# printer.net
KiCad netlist of a schematic drawn in EAGLE
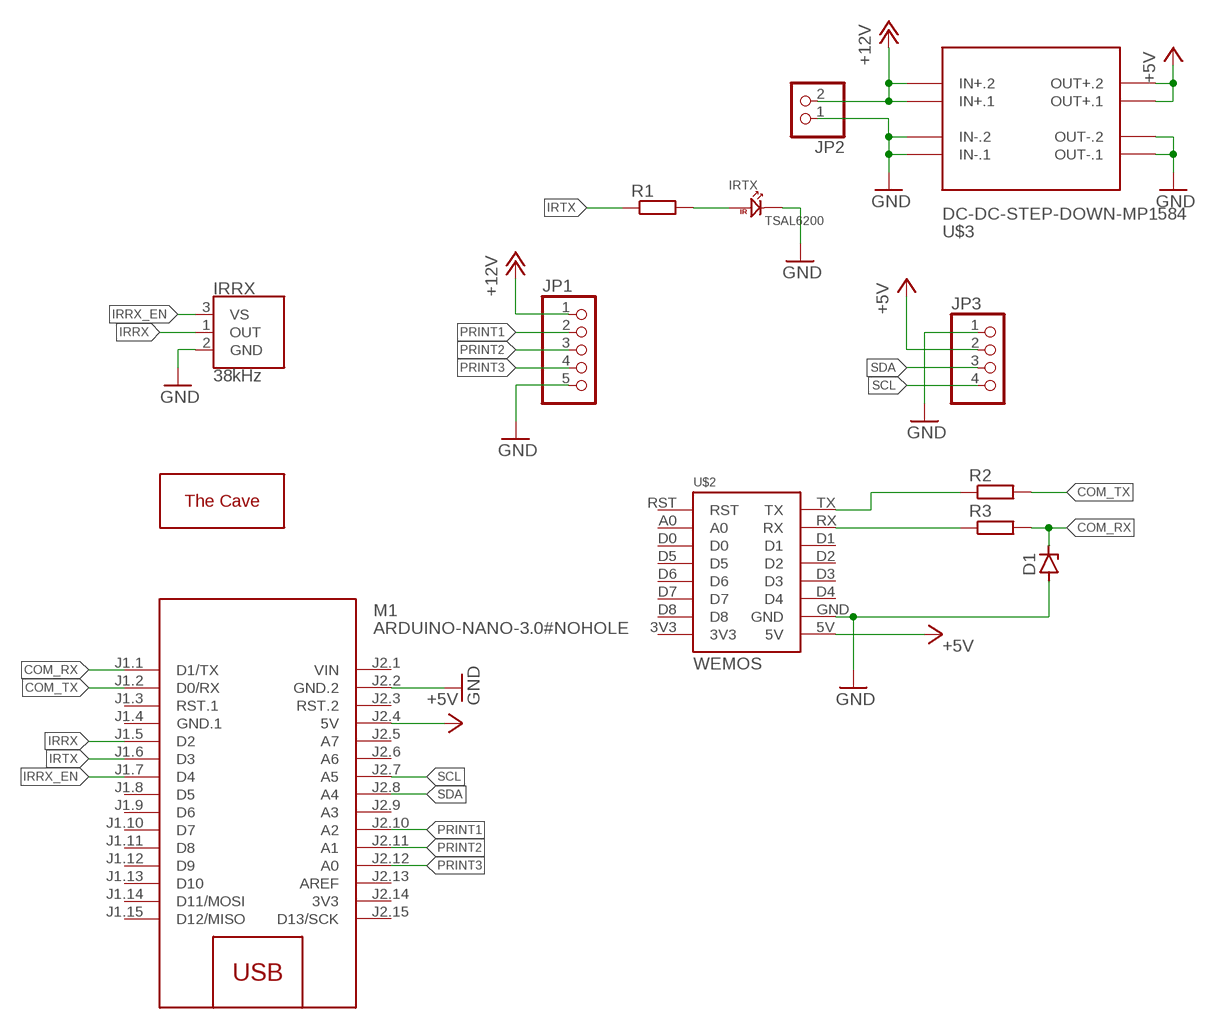
[diagram p0: schematic, sheet 1]

(export (version "E")
  (design (tool "Eeschema 10.0.6"))
  (components
    (comp (ref "D1")
      (value "ZENER-DIODEDO34-7")
      (footprint "eagle-import:DO34Z7")
      (libsource (lib "eagle-import") (part "ZENER-DIODEDO34-7"))
    )
    (comp (ref "IRRX")
      (value "38kHz")
      (footprint "eagle-import:TSOP382")
      (libsource (lib "eagle-import") (part "TSOP38238"))
    )
    (comp (ref "IRTX")
      (value "TSAL6200")
      (footprint "eagle-import:TSAL6200")
      (libsource (lib "eagle-import") (part "TSAL6200"))
    )
    (comp (ref "JP1")
      (value "PINHD-1X5")
      (footprint "eagle-import:1X05")
      (libsource (lib "eagle-import") (part "PINHD-1X5"))
    )
    (comp (ref "JP2")
      (value "PINHD-1X2")
      (footprint "eagle-import:1X02")
      (libsource (lib "eagle-import") (part "PINHD-1X2"))
    )
    (comp (ref "JP3")
      (value "PINHD-1X4")
      (footprint "eagle-import:1X04")
      (libsource (lib "eagle-import") (part "PINHD-1X4"))
    )
    (comp (ref "M1")
      (value "ARDUINO-NANO-3.0#NOHOLE")
      (footprint "eagle-import:ARDUINO-NANO-3.0")
      (libsource (lib "eagle-import") (part "ARDUINO-NANO-3.0#NOHOLE"))
    )
    (comp (ref "R1")
      (value "R-EU_0207/7")
      (footprint "eagle-import:0207_7")
      (libsource (lib "eagle-import") (part "R-EU_0207/7"))
    )
    (comp (ref "R2")
      (value "R-EU_0207/7")
      (footprint "eagle-import:0207_7")
      (libsource (lib "eagle-import") (part "R-EU_0207/7"))
    )
    (comp (ref "R3")
      (value "R-EU_0207/7")
      (footprint "eagle-import:0207_7")
      (libsource (lib "eagle-import") (part "R-EU_0207/7"))
    )
    (comp (ref "U$2")
      (value "WEMOS")
      (footprint "eagle-import:WEMOS")
      (libsource (lib "eagle-import") (part "WEMOS"))
    )
    (comp (ref "U$3")
      (value "DC-DC-STEP-DOWN-MP1584")
      (footprint "eagle-import:DC-DC-STEP-DOWN-MP1584")
      (libsource (lib "eagle-import") (part "DC-DC-STEP-DOWN-MP1584"))
    )
    (comp (ref "U$4")
      (value "THECAVE_LOGO_NEW_BOTTOM")
      (footprint "eagle-import:NEW_LOGO_BOTTOM")
      (libsource (lib "eagle-import") (part "THECAVE_LOGO_NEW_BOTTOM"))
    )
  )
  (nets
    (net (code "1") (name "+5V") (class "Default")
      (node (ref "JP3") (pin "2") (pinfunction "2_2") (pintype "passive"))
      (node (ref "M1") (pin "J2.4") (pinfunction "5V_J2.4") (pintype "power_in"))
      (node (ref "U$2") (pin "5V") (pinfunction "5V_5V") (pintype "bidirectional"))
      (node (ref "U$3") (pin "OUT+.1") (pinfunction "OUT+.1_OUT+.1") (pintype "bidirectional"))
      (node (ref "U$3") (pin "OUT+.2") (pinfunction "OUT+.2_OUT+.2") (pintype "bidirectional"))
    )
    (net (code "2") (name "+12V") (class "Default")
      (node (ref "JP1") (pin "1") (pinfunction "1_1") (pintype "passive"))
      (node (ref "JP2") (pin "2") (pinfunction "2_2") (pintype "passive"))
      (node (ref "U$3") (pin "IN+.1") (pinfunction "IN+.1_IN+.1") (pintype "bidirectional"))
      (node (ref "U$3") (pin "IN+.2") (pinfunction "IN+.2_IN+.2") (pintype "bidirectional"))
    )
    (net (code "3") (name "/3V3") (class "Default")
      (node (ref "M1") (pin "J2.14") (pinfunction "3V3_J2.14") (pintype "power_in"))
    )
    (net (code "4") (name "/GND.1") (class "Default")
      (node (ref "M1") (pin "J1.4") (pinfunction "GND.1_J1.4") (pintype "power_in"))
    )
    (net (code "5") (name "/VIN") (class "Default")
      (node (ref "M1") (pin "J2.1") (pinfunction "VIN_J2.1") (pintype "power_in"))
    )
    (net (code "6") (name "COM_RX") (class "Default")
      (node (ref "D1") (pin "C") (pinfunction "C_C") (pintype "passive"))
      (node (ref "M1") (pin "J1.1") (pinfunction "D1/TX_J1.1") (pintype "bidirectional"))
      (node (ref "R3") (pin "2") (pinfunction "2_2") (pintype "passive"))
    )
    (net (code "7") (name "COM_TX") (class "Default")
      (node (ref "M1") (pin "J1.2") (pinfunction "D0/RX_J1.2") (pintype "bidirectional"))
      (node (ref "R2") (pin "2") (pinfunction "2_2") (pintype "passive"))
    )
    (net (code "8") (name "GND") (class "Default")
      (node (ref "D1") (pin "A") (pinfunction "A_A") (pintype "passive"))
      (node (ref "IRRX") (pin "2") (pinfunction "GND_2") (pintype "bidirectional"))
      (node (ref "IRTX") (pin "N") (pinfunction "N_N") (pintype "bidirectional"))
      (node (ref "JP1") (pin "5") (pinfunction "5_5") (pintype "passive"))
      (node (ref "JP2") (pin "1") (pinfunction "1_1") (pintype "passive"))
      (node (ref "JP3") (pin "1") (pinfunction "1_1") (pintype "passive"))
      (node (ref "M1") (pin "J2.2") (pinfunction "GND.2_J2.2") (pintype "power_in"))
      (node (ref "U$2") (pin "GND") (pinfunction "GND_GND") (pintype "bidirectional"))
      (node (ref "U$3") (pin "IN-.1") (pinfunction "IN-.1_IN-.1") (pintype "bidirectional"))
      (node (ref "U$3") (pin "IN-.2") (pinfunction "IN-.2_IN-.2") (pintype "bidirectional"))
      (node (ref "U$3") (pin "OUT-.1") (pinfunction "OUT-.1_OUT-.1") (pintype "bidirectional"))
      (node (ref "U$3") (pin "OUT-.2") (pinfunction "OUT-.2_OUT-.2") (pintype "bidirectional"))
    )
    (net (code "9") (name "IRRX") (class "Default")
      (node (ref "IRRX") (pin "1") (pinfunction "OUT_1") (pintype "bidirectional"))
      (node (ref "M1") (pin "J1.5") (pinfunction "D2_J1.5") (pintype "bidirectional"))
    )
    (net (code "10") (name "IRRX_EN") (class "Default")
      (node (ref "IRRX") (pin "3") (pinfunction "VS_3") (pintype "bidirectional"))
      (node (ref "M1") (pin "J1.7") (pinfunction "D4_J1.7") (pintype "bidirectional"))
    )
    (net (code "11") (name "IRTX") (class "Default")
      (node (ref "M1") (pin "J1.6") (pinfunction "D3_J1.6") (pintype "bidirectional"))
      (node (ref "R1") (pin "1") (pinfunction "1_1") (pintype "passive"))
    )
    (net (code "12") (name "Net-(IRTX-PadP)") (class "Default")
      (node (ref "IRTX") (pin "P") (pinfunction "P_P") (pintype "bidirectional"))
      (node (ref "R1") (pin "2") (pinfunction "2_2") (pintype "passive"))
    )
    (net (code "13") (name "Net-(R2-Pad1)") (class "Default")
      (node (ref "R2") (pin "1") (pinfunction "1_1") (pintype "passive"))
      (node (ref "U$2") (pin "TX") (pinfunction "TX_TX") (pintype "bidirectional"))
    )
    (net (code "14") (name "Net-(R3-Pad1)") (class "Default")
      (node (ref "R3") (pin "1") (pinfunction "1_1") (pintype "passive"))
      (node (ref "U$2") (pin "RX") (pinfunction "RX_RX") (pintype "bidirectional"))
    )
    (net (code "15") (name "PRINT1") (class "Default")
      (node (ref "JP1") (pin "2") (pinfunction "2_2") (pintype "passive"))
      (node (ref "M1") (pin "J2.10") (pinfunction "A2_J2.10") (pintype "bidirectional"))
    )
    (net (code "16") (name "PRINT2") (class "Default")
      (node (ref "JP1") (pin "3") (pinfunction "3_3") (pintype "passive"))
      (node (ref "M1") (pin "J2.11") (pinfunction "A1_J2.11") (pintype "bidirectional"))
    )
    (net (code "17") (name "PRINT3") (class "Default")
      (node (ref "JP1") (pin "4") (pinfunction "4_4") (pintype "passive"))
      (node (ref "M1") (pin "J2.12") (pinfunction "A0_J2.12") (pintype "bidirectional"))
    )
    (net (code "18") (name "SCL") (class "Default")
      (node (ref "JP3") (pin "4") (pinfunction "4_4") (pintype "passive"))
      (node (ref "M1") (pin "J2.7") (pinfunction "A5_J2.7") (pintype "bidirectional"))
    )
    (net (code "19") (name "SDA") (class "Default")
      (node (ref "JP3") (pin "3") (pinfunction "3_3") (pintype "passive"))
      (node (ref "M1") (pin "J2.8") (pinfunction "A4_J2.8") (pintype "bidirectional"))
    )
    (net (code "20") (name "unconnected-(M1-A3-PadJ2.9)") (class "Default")
      (node (ref "M1") (pin "J2.9") (pinfunction "A3_J2.9") (pintype "bidirectional"))
    )
    (net (code "21") (name "unconnected-(M1-A6-PadJ2.6)") (class "Default")
      (node (ref "M1") (pin "J2.6") (pinfunction "A6_J2.6") (pintype "bidirectional"))
    )
    (net (code "22") (name "unconnected-(M1-A7-PadJ2.5)") (class "Default")
      (node (ref "M1") (pin "J2.5") (pinfunction "A7_J2.5") (pintype "bidirectional"))
    )
    (net (code "23") (name "unconnected-(M1-AREF-PadJ2.13)") (class "Default")
      (node (ref "M1") (pin "J2.13") (pinfunction "AREF_J2.13") (pintype "bidirectional"))
    )
    (net (code "24") (name "unconnected-(M1-D5-PadJ1.8)") (class "Default")
      (node (ref "M1") (pin "J1.8") (pinfunction "D5_J1.8") (pintype "bidirectional"))
    )
    (net (code "25") (name "unconnected-(M1-D6-PadJ1.9)") (class "Default")
      (node (ref "M1") (pin "J1.9") (pinfunction "D6_J1.9") (pintype "bidirectional"))
    )
    (net (code "26") (name "unconnected-(M1-D7-PadJ1.10)") (class "Default")
      (node (ref "M1") (pin "J1.10") (pinfunction "D7_J1.10") (pintype "bidirectional"))
    )
    (net (code "27") (name "unconnected-(M1-D8-PadJ1.11)") (class "Default")
      (node (ref "M1") (pin "J1.11") (pinfunction "D8_J1.11") (pintype "bidirectional"))
    )
    (net (code "28") (name "unconnected-(M1-D9-PadJ1.12)") (class "Default")
      (node (ref "M1") (pin "J1.12") (pinfunction "D9_J1.12") (pintype "bidirectional"))
    )
    (net (code "29") (name "unconnected-(M1-D10-PadJ1.13)") (class "Default")
      (node (ref "M1") (pin "J1.13") (pinfunction "D10_J1.13") (pintype "bidirectional"))
    )
    (net (code "30") (name "unconnected-(M1-D11{slash}MOSI-PadJ1.14)") (class "Default")
      (node (ref "M1") (pin "J1.14") (pinfunction "D11/MOSI_J1.14") (pintype "bidirectional"))
    )
    (net (code "31") (name "unconnected-(M1-D12{slash}MISO-PadJ1.15)") (class "Default")
      (node (ref "M1") (pin "J1.15") (pinfunction "D12/MISO_J1.15") (pintype "bidirectional"))
    )
    (net (code "32") (name "unconnected-(M1-D13{slash}SCK-PadJ2.15)") (class "Default")
      (node (ref "M1") (pin "J2.15") (pinfunction "D13/SCK_J2.15") (pintype "bidirectional"))
    )
    (net (code "33") (name "unconnected-(M1-RST.1-PadJ1.3)") (class "Default")
      (node (ref "M1") (pin "J1.3") (pinfunction "RST.1_J1.3") (pintype "bidirectional"))
    )
    (net (code "34") (name "unconnected-(M1-RST.2-PadJ2.3)") (class "Default")
      (node (ref "M1") (pin "J2.3") (pinfunction "RST.2_J2.3") (pintype "bidirectional"))
    )
    (net (code "35") (name "unconnected-(U$2-Pad3V3)") (class "Default")
      (node (ref "U$2") (pin "3V3") (pinfunction "3V3_3V3") (pintype "bidirectional"))
    )
    (net (code "36") (name "unconnected-(U$2-PadA0)") (class "Default")
      (node (ref "U$2") (pin "A0") (pinfunction "A0_A0") (pintype "bidirectional"))
    )
    (net (code "37") (name "unconnected-(U$2-PadD0)") (class "Default")
      (node (ref "U$2") (pin "D0") (pinfunction "D0_D0") (pintype "bidirectional"))
    )
    (net (code "38") (name "unconnected-(U$2-PadD1)") (class "Default")
      (node (ref "U$2") (pin "D1") (pinfunction "D1_D1") (pintype "bidirectional"))
    )
    (net (code "39") (name "unconnected-(U$2-PadD2)") (class "Default")
      (node (ref "U$2") (pin "D2") (pinfunction "D2_D2") (pintype "bidirectional"))
    )
    (net (code "40") (name "unconnected-(U$2-PadD3)") (class "Default")
      (node (ref "U$2") (pin "D3") (pinfunction "D3_D3") (pintype "bidirectional"))
    )
    (net (code "41") (name "unconnected-(U$2-PadD4)") (class "Default")
      (node (ref "U$2") (pin "D4") (pinfunction "D4_D4") (pintype "bidirectional"))
    )
    (net (code "42") (name "unconnected-(U$2-PadD5)") (class "Default")
      (node (ref "U$2") (pin "D5") (pinfunction "D5_D5") (pintype "bidirectional"))
    )
    (net (code "43") (name "unconnected-(U$2-PadD6)") (class "Default")
      (node (ref "U$2") (pin "D6") (pinfunction "D6_D6") (pintype "bidirectional"))
    )
    (net (code "44") (name "unconnected-(U$2-PadD7)") (class "Default")
      (node (ref "U$2") (pin "D7") (pinfunction "D7_D7") (pintype "bidirectional"))
    )
    (net (code "45") (name "unconnected-(U$2-PadD8)") (class "Default")
      (node (ref "U$2") (pin "D8") (pinfunction "D8_D8") (pintype "bidirectional"))
    )
    (net (code "46") (name "unconnected-(U$2-PadRST)") (class "Default")
      (node (ref "U$2") (pin "RST") (pinfunction "RST_RST") (pintype "bidirectional"))
    )
  )
)
